# Nixie1.net
KiCad netlist of a schematic drawn in Altium Designer
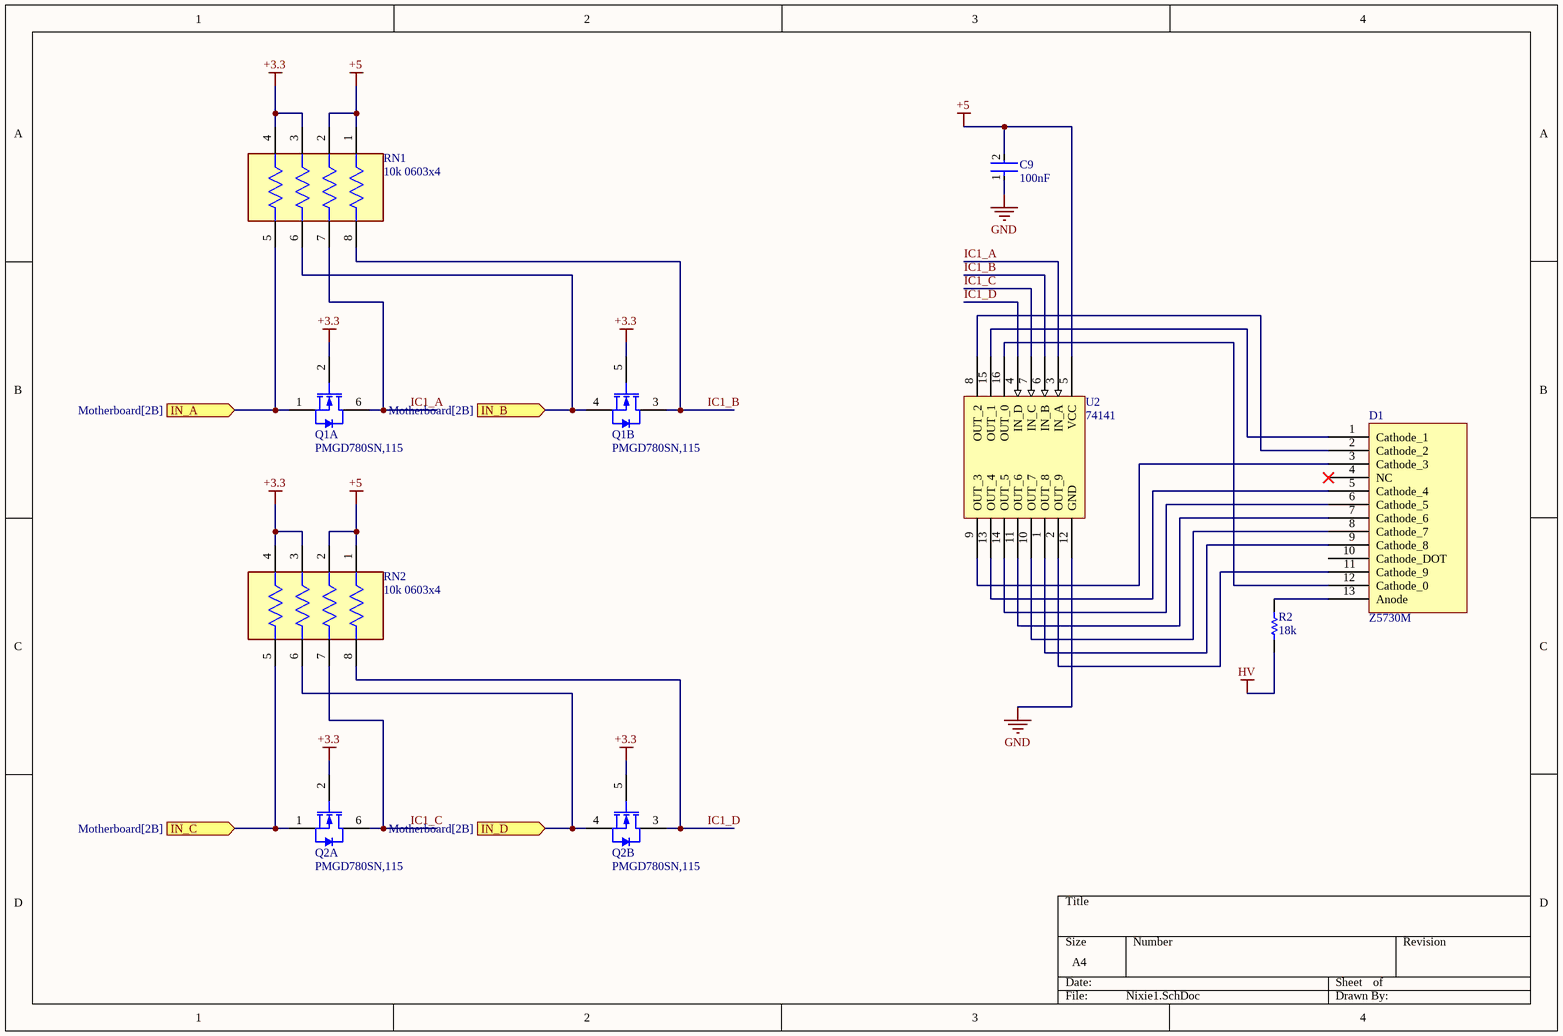
[diagram p0: Nixie1.SchDoc]

(export (version "E")
  (design (tool "Eeschema 10.0.6"))
  (components
    (comp (ref "C9")
      (value "100nF")
      (footprint "FP-C1005-050-0_15-MFG")
      (description "CAP CER 100nF 10V X5R 0402")
      (fields (field (name "TOLERANCE") "20%") (field (name "VOLTAGE") "10V"))
      (libsource (lib "Altium Content Vault") (part "11868f565c42a9108669ba33697ecf6"))
    )
    (comp (ref "D1") (value "Z5730M") (footprint "Z5730M") (libsource (lib "Z5730M") (part "Z5730M")))
    (comp (ref "Q1")
      (value "PMGD780SN,115")
      (footprint "NXP-SOT363_N")
      (description "Dual N-Channel uTrenchMOS Standard Level FET, 60 V, 0.49 A, 6-Pin SOT363, Tape and Reel")
      (fields (field (name "MANUFACTURER") "NXP Semiconductors"))
      (libsource (lib "Altium Content Vault") (part "NXP-NNMOS-SGDSGD-6_B"))
    )
    (comp (ref "Q2")
      (value "PMGD780SN,115")
      (footprint "NXP-SOT363_N")
      (description "Dual N-Channel uTrenchMOS Standard Level FET, 60 V, 0.49 A, 6-Pin SOT363, Tape and Reel")
      (fields (field (name "MANUFACTURER") "NXP Semiconductors"))
      (libsource (lib "Altium Content Vault") (part "NXP-NNMOS-SGDSGD-6_B"))
    )
    (comp (ref "R2")
      (value "18k")
      (footprint "RESC2013X60X40LL20T25")
      (fields (field (name "MANUFACTURER") "Panasonic") (field (name "PART NUMBER") "ERA6AEB183V"))
      (libsource (lib "Altium Content Vault") (part "RES"))
    )
    (comp (ref "RN1")
      (value "10k 0603x4")
      (footprint "FP-EXB38V-MFG")
      (description "RES ARRAY 4 RES 10K OHM 1206\r\nRC-ML08W103JT")
      (fields (field (name "TOLERANCE") "5%"))
      (libsource (lib "Altium Content Vault") (part "2ca08171d0bbdee8be62227dae509d7"))
    )
    (comp (ref "RN2")
      (value "10k 0603x4")
      (footprint "FP-EXB38V-MFG")
      (description "RES ARRAY 4 RES 10K OHM 1206\r\nRC-ML08W103JT")
      (fields (field (name "TOLERANCE") "5%"))
      (libsource (lib "Altium Content Vault") (part "2ca08171d0bbdee8be62227dae509d7"))
    )
    (comp (ref "U2") (value "74141") (footprint "DIP-16") (libsource (lib "Z5730M") (part "74141")))
  )
  (nets
    (net (code "1") (name "+3.3") (class "Default")
      (node (ref "Q1") (pin "2") (pinfunction "G1_2") (pintype "passive"))
      (node (ref "Q1") (pin "5") (pinfunction "G2_5") (pintype "passive"))
      (node (ref "Q2") (pin "2") (pinfunction "G1_2") (pintype "passive"))
      (node (ref "Q2") (pin "5") (pinfunction "G2_5") (pintype "passive"))
      (node (ref "RN1") (pin "3") (pinfunction "3_3") (pintype "passive"))
      (node (ref "RN1") (pin "4") (pinfunction "4_4") (pintype "passive"))
      (node (ref "RN2") (pin "3") (pinfunction "3_3") (pintype "passive"))
      (node (ref "RN2") (pin "4") (pinfunction "4_4") (pintype "passive"))
    )
    (net (code "2") (name "+5") (class "Default")
      (node (ref "C9") (pin "2") (pinfunction "2_2") (pintype "passive"))
      (node (ref "RN1") (pin "1") (pinfunction "1_1") (pintype "passive"))
      (node (ref "RN1") (pin "2") (pinfunction "2_2") (pintype "passive"))
      (node (ref "RN2") (pin "1") (pinfunction "1_1") (pintype "passive"))
      (node (ref "RN2") (pin "2") (pinfunction "2_2") (pintype "passive"))
      (node (ref "U2") (pin "5") (pinfunction "VCC_5") (pintype "power_in"))
    )
    (net (code "3") (name "/IC1_A") (class "Default")
      (node (ref "Q1") (pin "6") (pinfunction "D1_6") (pintype "passive"))
      (node (ref "RN1") (pin "7") (pinfunction "7_7") (pintype "passive"))
      (node (ref "U2") (pin "3") (pinfunction "IN_A_3") (pintype "input"))
    )
    (net (code "4") (name "/IC1_B") (class "Default")
      (node (ref "Q1") (pin "3") (pinfunction "D2_3") (pintype "passive"))
      (node (ref "RN1") (pin "8") (pinfunction "8_8") (pintype "passive"))
      (node (ref "U2") (pin "6") (pinfunction "IN_B_6") (pintype "input"))
    )
    (net (code "5") (name "/IC1_C") (class "Default")
      (node (ref "Q2") (pin "6") (pinfunction "D1_6") (pintype "passive"))
      (node (ref "RN2") (pin "7") (pinfunction "7_7") (pintype "passive"))
      (node (ref "U2") (pin "7") (pinfunction "IN_C_7") (pintype "input"))
    )
    (net (code "6") (name "/IC1_D") (class "Default")
      (node (ref "Q2") (pin "3") (pinfunction "D2_3") (pintype "passive"))
      (node (ref "RN2") (pin "8") (pinfunction "8_8") (pintype "passive"))
      (node (ref "U2") (pin "4") (pinfunction "IN_D_4") (pintype "input"))
    )
    (net (code "7") (name "/IN_A") (class "Default")
      (node (ref "Q1") (pin "1") (pinfunction "S1_1") (pintype "passive"))
      (node (ref "RN1") (pin "5") (pinfunction "5_5") (pintype "passive"))
    )
    (net (code "8") (name "/IN_B") (class "Default")
      (node (ref "Q1") (pin "4") (pinfunction "S2_4") (pintype "passive"))
      (node (ref "RN1") (pin "6") (pinfunction "6_6") (pintype "passive"))
    )
    (net (code "9") (name "/IN_C") (class "Default")
      (node (ref "Q2") (pin "1") (pinfunction "S1_1") (pintype "passive"))
      (node (ref "RN2") (pin "5") (pinfunction "5_5") (pintype "passive"))
    )
    (net (code "10") (name "/IN_D") (class "Default")
      (node (ref "Q2") (pin "4") (pinfunction "S2_4") (pintype "passive"))
      (node (ref "RN2") (pin "6") (pinfunction "6_6") (pintype "passive"))
    )
    (net (code "11") (name "GND") (class "Default")
      (node (ref "C9") (pin "1") (pinfunction "1_1") (pintype "passive"))
      (node (ref "U2") (pin "12") (pinfunction "GND_12") (pintype "power_in"))
    )
    (net (code "12") (name "HV") (class "Default")
      (node (ref "R2") (pin "1") (pinfunction "1_1") (pintype "passive"))
    )
    (net (code "13") (name "Net-(D1-Anode)") (class "Default")
      (node (ref "D1") (pin "13") (pinfunction "Anode_13") (pintype "passive"))
      (node (ref "R2") (pin "2") (pinfunction "2_2") (pintype "passive"))
    )
    (net (code "14") (name "Net-(D1-Cathode_0)") (class "Default")
      (node (ref "D1") (pin "12") (pinfunction "Cathode_0_12") (pintype "passive"))
      (node (ref "U2") (pin "16") (pinfunction "OUT_0_16") (pintype "open_collector"))
    )
    (net (code "15") (name "Net-(D1-Cathode_1)") (class "Default")
      (node (ref "D1") (pin "1") (pinfunction "Cathode_1_1") (pintype "passive"))
      (node (ref "U2") (pin "15") (pinfunction "OUT_1_15") (pintype "open_collector"))
    )
    (net (code "16") (name "Net-(D1-Cathode_2)") (class "Default")
      (node (ref "D1") (pin "2") (pinfunction "Cathode_2_2") (pintype "passive"))
      (node (ref "U2") (pin "8") (pinfunction "OUT_2_8") (pintype "open_collector"))
    )
    (net (code "17") (name "Net-(D1-Cathode_3)") (class "Default")
      (node (ref "D1") (pin "3") (pinfunction "Cathode_3_3") (pintype "passive"))
      (node (ref "U2") (pin "9") (pinfunction "OUT_3_9") (pintype "open_collector"))
    )
    (net (code "18") (name "Net-(D1-Cathode_4)") (class "Default")
      (node (ref "D1") (pin "5") (pinfunction "Cathode_4_5") (pintype "passive"))
      (node (ref "U2") (pin "13") (pinfunction "OUT_4_13") (pintype "open_collector"))
    )
    (net (code "19") (name "Net-(D1-Cathode_5)") (class "Default")
      (node (ref "D1") (pin "6") (pinfunction "Cathode_5_6") (pintype "passive"))
      (node (ref "U2") (pin "14") (pinfunction "OUT_5_14") (pintype "open_collector"))
    )
    (net (code "20") (name "Net-(D1-Cathode_6)") (class "Default")
      (node (ref "D1") (pin "7") (pinfunction "Cathode_6_7") (pintype "passive"))
      (node (ref "U2") (pin "11") (pinfunction "OUT_6_11") (pintype "open_collector"))
    )
    (net (code "21") (name "Net-(D1-Cathode_7)") (class "Default")
      (node (ref "D1") (pin "8") (pinfunction "Cathode_7_8") (pintype "passive"))
      (node (ref "U2") (pin "10") (pinfunction "OUT_7_10") (pintype "open_collector"))
    )
    (net (code "22") (name "Net-(D1-Cathode_8)") (class "Default")
      (node (ref "D1") (pin "9") (pinfunction "Cathode_8_9") (pintype "passive"))
      (node (ref "U2") (pin "1") (pinfunction "OUT_8_1") (pintype "open_collector"))
    )
    (net (code "23") (name "Net-(D1-Cathode_9)") (class "Default")
      (node (ref "D1") (pin "11") (pinfunction "Cathode_9_11") (pintype "passive"))
      (node (ref "U2") (pin "2") (pinfunction "OUT_9_2") (pintype "open_collector"))
    )
    (net (code "24") (name "unconnected-(D1-Cathode_DOT-Pad10)") (class "Default")
      (node (ref "D1") (pin "10") (pinfunction "Cathode_DOT_10") (pintype "passive"))
    )
    (net (code "25") (name "unconnected-(D1-NC-Pad4)") (class "Default")
      (node (ref "D1") (pin "4") (pinfunction "NC_4") (pintype "passive+no_connect"))
    )
  )
)
